# NoWaterNoNo.net
KiCad netlist of a schematic drawn in EAGLE
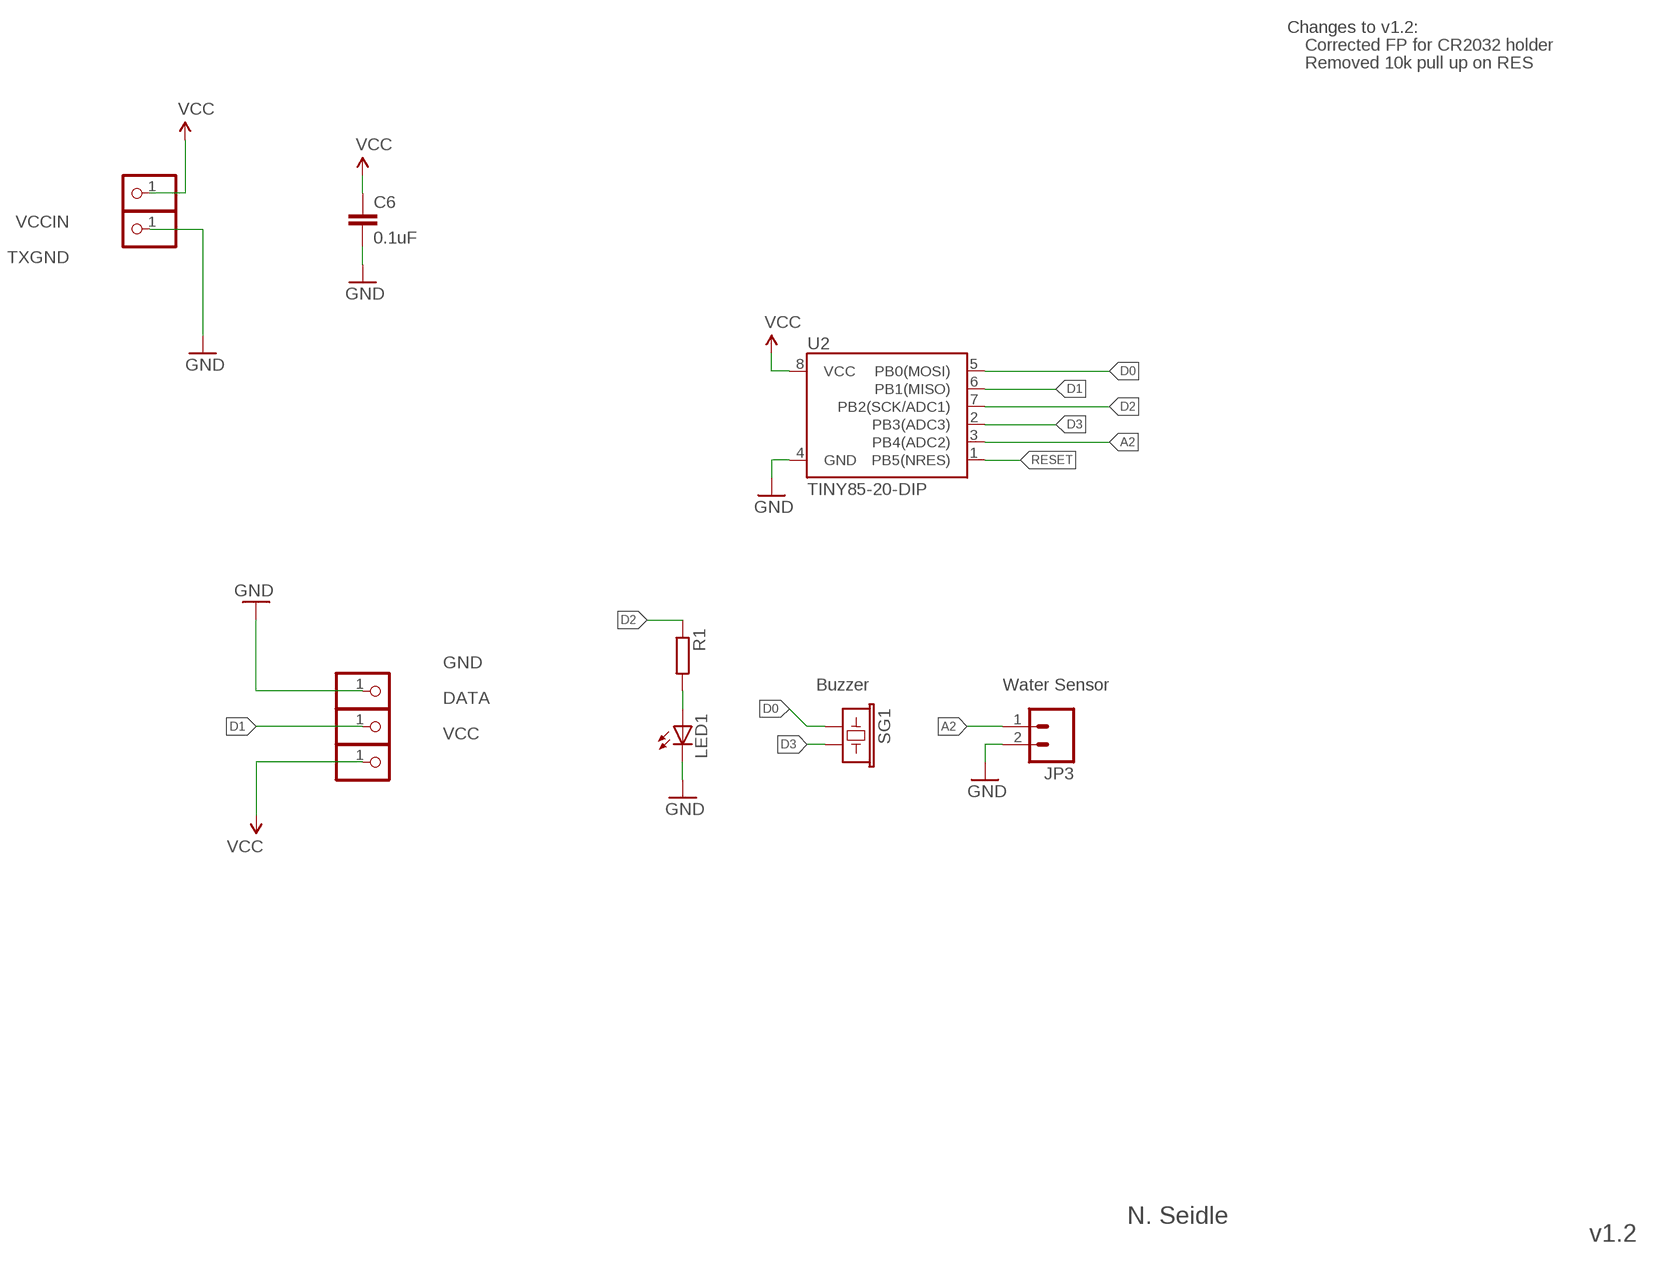
[diagram p0: schematic, sheet 1]

(export (version "E")
  (design (tool "Eeschema 10.0.6"))
  (components
    (comp (ref "C6")
      (value "0.1uF")
      (footprint "eagle-import:CAP-PTH-SMALL2")
      (libsource (lib "eagle-import") (part "CAPPTH2"))
    )
    (comp (ref "DATA")
      (value "PINHD-1X1")
      (footprint "eagle-import:1X01")
      (libsource (lib "eagle-import") (part "PINHD-1X1"))
    )
    (comp (ref "GND")
      (value "PINHD-1X1")
      (footprint "eagle-import:1X01")
      (libsource (lib "eagle-import") (part "PINHD-1X1"))
    )
    (comp (ref "JP3")
      (value "Water Sensor")
      (footprint "eagle-import:1X02")
      (libsource (lib "eagle-import") (part "M02PTH"))
    )
    (comp (ref "LED1")
      (value "LED5MM")
      (footprint "eagle-import:LED5MM")
      (libsource (lib "eagle-import") (part "LED5MM"))
    )
    (comp (ref "R1")
      (value "R-EU_0204/2V")
      (footprint "eagle-import:0204V")
      (libsource (lib "eagle-import") (part "R-EU_0204/2V"))
    )
    (comp (ref "SG1")
      (value "Buzzer")
      (footprint "eagle-import:BUZZER-12MM")
      (libsource (lib "eagle-import") (part "BUZZERPTH"))
    )
    (comp (ref "TXGND")
      (value "PINHD-1X1")
      (footprint "eagle-import:1X01")
      (libsource (lib "eagle-import") (part "PINHD-1X1"))
    )
    (comp (ref "U2")
      (value "TINY85-20-DIP")
      (footprint "eagle-import:DIP08")
      (fields (field (name "PROD_ID") "IC-09445"))
      (libsource (lib "eagle-import") (part "ATTINY45TINY85-20-DIP"))
    )
    (comp (ref "VCC")
      (value "PINHD-1X1")
      (footprint "eagle-import:1X01")
      (libsource (lib "eagle-import") (part "PINHD-1X1"))
    )
    (comp (ref "VCCIN")
      (value "PINHD-1X1")
      (footprint "eagle-import:1X01")
      (libsource (lib "eagle-import") (part "PINHD-1X1"))
    )
  )
  (nets
    (net (code "1") (name "A2") (class "Default")
      (node (ref "JP3") (pin "1") (pinfunction "1_1") (pintype "passive"))
      (node (ref "U2") (pin "3") (pinfunction "PB4(ADC2)_3") (pintype "bidirectional"))
    )
    (net (code "2") (name "D0") (class "Default")
      (node (ref "SG1") (pin "+") (pinfunction "1_+") (pintype "passive"))
      (node (ref "U2") (pin "5") (pinfunction "PB0(MOSI)_5") (pintype "bidirectional"))
    )
    (net (code "3") (name "D1") (class "Default")
      (node (ref "DATA") (pin "1") (pinfunction "1_1") (pintype "passive"))
      (node (ref "U2") (pin "6") (pinfunction "PB1(MISO)_6") (pintype "bidirectional"))
    )
    (net (code "4") (name "D2") (class "Default")
      (node (ref "R1") (pin "1") (pinfunction "1_1") (pintype "passive"))
      (node (ref "U2") (pin "7") (pinfunction "PB2(SCK/ADC1)_7") (pintype "bidirectional"))
    )
    (net (code "5") (name "D3") (class "Default")
      (node (ref "SG1") (pin "-") (pinfunction "2_-") (pintype "passive"))
      (node (ref "U2") (pin "2") (pinfunction "PB3(ADC3)_2") (pintype "bidirectional"))
    )
    (net (code "6") (name "GND") (class "Default")
      (node (ref "C6") (pin "2") (pinfunction "2_2") (pintype "passive"))
      (node (ref "GND") (pin "1") (pinfunction "1_1") (pintype "passive"))
      (node (ref "JP3") (pin "2") (pinfunction "2_2") (pintype "passive"))
      (node (ref "LED1") (pin "K") (pinfunction "C_K") (pintype "passive"))
      (node (ref "TXGND") (pin "1") (pinfunction "1_1") (pintype "passive"))
      (node (ref "U2") (pin "4") (pinfunction "GND_4") (pintype "bidirectional"))
    )
    (net (code "7") (name "Net-(LED1-PadA)") (class "Default")
      (node (ref "LED1") (pin "A") (pinfunction "A_A") (pintype "passive"))
      (node (ref "R1") (pin "2") (pinfunction "2_2") (pintype "passive"))
    )
    (net (code "8") (name "RESET") (class "Default")
      (node (ref "U2") (pin "1") (pinfunction "PB5(NRES)_1") (pintype "bidirectional"))
    )
    (net (code "9") (name "VCC") (class "Default")
      (node (ref "C6") (pin "1") (pinfunction "1_1") (pintype "passive"))
      (node (ref "U2") (pin "8") (pinfunction "VCC_8") (pintype "bidirectional"))
      (node (ref "VCC") (pin "1") (pinfunction "1_1") (pintype "passive"))
      (node (ref "VCCIN") (pin "1") (pinfunction "1_1") (pintype "passive"))
    )
  )
)
